# double-tube-base.net
KiCad netlist of a schematic drawn in EAGLE
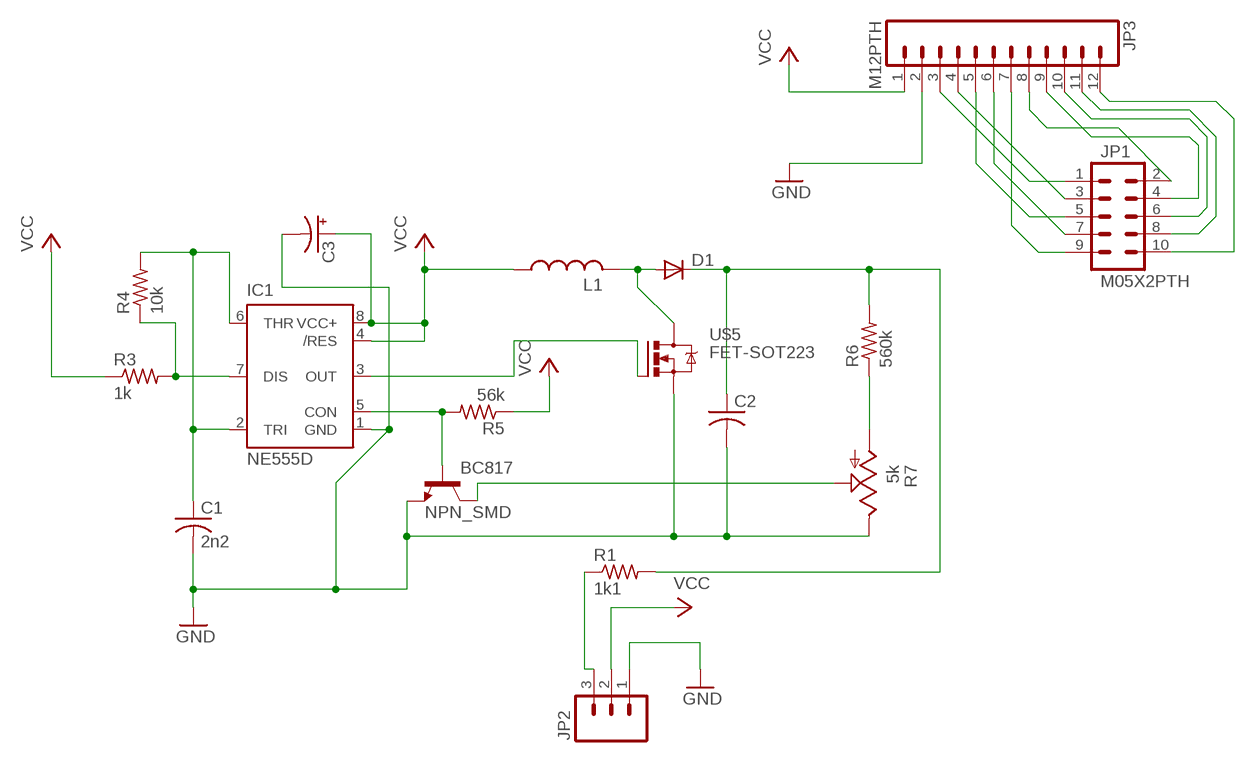
[diagram p0: schematic, sheet 1]

(export (version "E")
  (design (tool "Eeschema 10.0.6"))
  (components
    (comp (ref "BC817")
      (value "NPN_SMD")
      (footprint "eagle-import:SOT-23")
      (libsource (lib "eagle-import") (part "NPN_SMD"))
    )
    (comp (ref "C1")
      (value "2n2")
      (footprint "eagle-import:C0603K")
      (libsource (lib "eagle-import") (part "CAPACITORC0603K"))
    )
    (comp (ref "C2")
      (value "CAPACITORC1812K")
      (footprint "eagle-import:C1812K")
      (libsource (lib "eagle-import") (part "CAPACITORC1812K"))
    )
    (comp (ref "C3")
      (value "CAPACITOR_POLSMCD")
      (footprint "eagle-import:SMC_D")
      (libsource (lib "eagle-import") (part "CAPACITOR_POLSMCD"))
    )
    (comp (ref "D1")
      (value "DIODESMA")
      (footprint "eagle-import:SMA-DIODE")
      (libsource (lib "eagle-import") (part "DIODESMA"))
    )
    (comp (ref "IC1")
      (value "NE555D")
      (footprint "eagle-import:SO08")
      (libsource (lib "eagle-import") (part "NE555D"))
    )
    (comp (ref "JP1")
      (value "M05X2PTH")
      (footprint "eagle-import:AVR_ICSP")
      (libsource (lib "eagle-import") (part "M05X2PTH"))
    )
    (comp (ref "JP2")
      (value "M03PTH")
      (footprint "eagle-import:1X03")
      (libsource (lib "eagle-import") (part "M03PTH"))
    )
    (comp (ref "JP3")
      (value "M12PTH")
      (footprint "eagle-import:1X12")
      (libsource (lib "eagle-import") (part "M12PTH"))
    )
    (comp (ref "L1")
      (value "INDUCTORSMD-10MM")
      (footprint "eagle-import:SMD-10MM")
      (libsource (lib "eagle-import") (part "INDUCTORSMD-10MM"))
    )
    (comp (ref "R1")
      (value "1k1")
      (footprint "eagle-import:R1206")
      (libsource (lib "eagle-import") (part "RESISTORR1206"))
    )
    (comp (ref "R3")
      (value "1k")
      (footprint "eagle-import:R0603")
      (libsource (lib "eagle-import") (part "RESISTORR0603"))
    )
    (comp (ref "R4")
      (value "10k")
      (footprint "eagle-import:R0603")
      (libsource (lib "eagle-import") (part "RESISTORR0603"))
    )
    (comp (ref "R5")
      (value "56k")
      (footprint "eagle-import:R0603")
      (libsource (lib "eagle-import") (part "RESISTORR0603"))
    )
    (comp (ref "R6")
      (value "560k")
      (footprint "eagle-import:R1206")
      (libsource (lib "eagle-import") (part "RESISTORR1206"))
    )
    (comp (ref "R7")
      (value "5k")
      (footprint "eagle-import:TRIM-EVM2N")
      (libsource (lib "eagle-import") (part "TRIM_POTEVM2N"))
    )
    (comp (ref "U$5")
      (value "FET-SOT223")
      (footprint "eagle-import:SOT-223")
      (libsource (lib "eagle-import") (part "FET-SOT223"))
    )
  )
  (nets
    (net (code "1") (name "GND") (class "Default")
      (node (ref "BC817") (pin "2") (pinfunction "E_2") (pintype "passive"))
      (node (ref "C1") (pin "2") (pinfunction "2_2") (pintype "passive"))
      (node (ref "C2") (pin "2") (pinfunction "2_2") (pintype "passive"))
      (node (ref "C3") (pin "-") (pinfunction "-_-") (pintype "passive"))
      (node (ref "IC1") (pin "1") (pinfunction "GND_1") (pintype "power_in"))
      (node (ref "JP2") (pin "1") (pinfunction "1_1") (pintype "passive"))
      (node (ref "JP3") (pin "2") (pinfunction "2_2") (pintype "passive"))
      (node (ref "R7") (pin "P$3") (pinfunction "E_P$3") (pintype "passive"))
      (node (ref "U$5") (pin "3") (pinfunction "S_3") (pintype "passive"))
    )
    (net (code "2") (name "Net-(BC817-B)") (class "Default")
      (node (ref "BC817") (pin "1") (pinfunction "B_1") (pintype "passive"))
      (node (ref "IC1") (pin "5") (pinfunction "CON_5") (pintype "input"))
      (node (ref "R5") (pin "2") (pinfunction "2_2") (pintype "passive"))
    )
    (net (code "3") (name "Net-(BC817-C)") (class "Default")
      (node (ref "BC817") (pin "3") (pinfunction "C_3") (pintype "passive"))
      (node (ref "R7") (pin "P$2") (pinfunction "S_P$2") (pintype "passive"))
    )
    (net (code "4") (name "Net-(C2-Pad1)") (class "Default")
      (node (ref "C2") (pin "1") (pinfunction "1_1") (pintype "passive"))
      (node (ref "D1") (pin "C") (pinfunction "C_C") (pintype "passive"))
      (node (ref "R1") (pin "2") (pinfunction "2_2") (pintype "passive"))
      (node (ref "R6") (pin "2") (pinfunction "2_2") (pintype "passive"))
    )
    (net (code "5") (name "Net-(IC1-DIS)") (class "Default")
      (node (ref "IC1") (pin "7") (pinfunction "DIS_7") (pintype "input"))
      (node (ref "R3") (pin "2") (pinfunction "2_2") (pintype "passive"))
      (node (ref "R4") (pin "1") (pinfunction "1_1") (pintype "passive"))
    )
    (net (code "6") (name "Net-(IC1-OUT)") (class "Default")
      (node (ref "IC1") (pin "3") (pinfunction "OUT_3") (pintype "output"))
      (node (ref "U$5") (pin "1") (pinfunction "G_1") (pintype "passive"))
    )
    (net (code "7") (name "Net-(IC1-THR)") (class "Default")
      (node (ref "C1") (pin "1") (pinfunction "1_1") (pintype "passive"))
      (node (ref "IC1") (pin "2") (pinfunction "TRI_2") (pintype "input"))
      (node (ref "IC1") (pin "6") (pinfunction "THR_6") (pintype "input"))
      (node (ref "R4") (pin "2") (pinfunction "2_2") (pintype "passive"))
    )
    (net (code "8") (name "Net-(JP1-Pad1)") (class "Default")
      (node (ref "JP1") (pin "1") (pinfunction "1_1") (pintype "passive"))
      (node (ref "JP3") (pin "3") (pinfunction "3_3") (pintype "passive"))
    )
    (net (code "9") (name "Net-(JP1-Pad2)") (class "Default")
      (node (ref "JP1") (pin "2") (pinfunction "2_2") (pintype "passive"))
      (node (ref "JP3") (pin "8") (pinfunction "8_8") (pintype "passive"))
    )
    (net (code "10") (name "Net-(JP1-Pad3)") (class "Default")
      (node (ref "JP1") (pin "3") (pinfunction "3_3") (pintype "passive"))
      (node (ref "JP3") (pin "4") (pinfunction "4_4") (pintype "passive"))
    )
    (net (code "11") (name "Net-(JP1-Pad4)") (class "Default")
      (node (ref "JP1") (pin "4") (pinfunction "4_4") (pintype "passive"))
      (node (ref "JP3") (pin "9") (pinfunction "9_9") (pintype "passive"))
    )
    (net (code "12") (name "Net-(JP1-Pad5)") (class "Default")
      (node (ref "JP1") (pin "5") (pinfunction "5_5") (pintype "passive"))
      (node (ref "JP3") (pin "5") (pinfunction "5_5") (pintype "passive"))
    )
    (net (code "13") (name "Net-(JP1-Pad6)") (class "Default")
      (node (ref "JP1") (pin "6") (pinfunction "6_6") (pintype "passive"))
      (node (ref "JP3") (pin "10") (pinfunction "10_10") (pintype "passive"))
    )
    (net (code "14") (name "Net-(JP1-Pad7)") (class "Default")
      (node (ref "JP1") (pin "7") (pinfunction "7_7") (pintype "passive"))
      (node (ref "JP3") (pin "6") (pinfunction "6_6") (pintype "passive"))
    )
    (net (code "15") (name "Net-(JP1-Pad8)") (class "Default")
      (node (ref "JP1") (pin "8") (pinfunction "8_8") (pintype "passive"))
      (node (ref "JP3") (pin "11") (pinfunction "11_11") (pintype "passive"))
    )
    (net (code "16") (name "Net-(JP1-Pad9)") (class "Default")
      (node (ref "JP1") (pin "9") (pinfunction "9_9") (pintype "passive"))
      (node (ref "JP3") (pin "7") (pinfunction "7_7") (pintype "passive"))
    )
    (net (code "17") (name "Net-(JP1-Pad10)") (class "Default")
      (node (ref "JP1") (pin "10") (pinfunction "10_10") (pintype "passive"))
      (node (ref "JP3") (pin "12") (pinfunction "12_12") (pintype "passive"))
    )
    (net (code "18") (name "Net-(JP2-Pad3)") (class "Default")
      (node (ref "JP2") (pin "3") (pinfunction "3_3") (pintype "passive"))
      (node (ref "R1") (pin "1") (pinfunction "1_1") (pintype "passive"))
    )
    (net (code "19") (name "Net-(L1-2)") (class "Default")
      (node (ref "D1") (pin "A") (pinfunction "A_A") (pintype "passive"))
      (node (ref "L1") (pin "P$2") (pinfunction "2_P$2") (pintype "passive"))
      (node (ref "U$5") (pin "2") (pinfunction "D_2") (pintype "passive"))
      (node (ref "U$5") (pin "4") (pinfunction "D_4") (pintype "passive"))
    )
    (net (code "20") (name "Net-(R7-A)") (class "Default")
      (node (ref "R6") (pin "1") (pinfunction "1_1") (pintype "passive"))
      (node (ref "R7") (pin "P$1") (pinfunction "A_P$1") (pintype "passive"))
    )
    (net (code "21") (name "VCC") (class "Default")
      (node (ref "C3") (pin "+") (pinfunction "+_+") (pintype "passive"))
      (node (ref "IC1") (pin "4") (pinfunction "/RES_4") (pintype "input"))
      (node (ref "IC1") (pin "8") (pinfunction "VCC+_8") (pintype "power_in"))
      (node (ref "JP2") (pin "2") (pinfunction "2_2") (pintype "passive"))
      (node (ref "JP3") (pin "1") (pinfunction "1_1") (pintype "passive"))
      (node (ref "L1") (pin "P$1") (pinfunction "1_P$1") (pintype "passive"))
      (node (ref "R3") (pin "1") (pinfunction "1_1") (pintype "passive"))
      (node (ref "R5") (pin "1") (pinfunction "1_1") (pintype "passive"))
    )
  )
)
